# controllerBackup.net
KiCad netlist of a schematic drawn in EAGLE
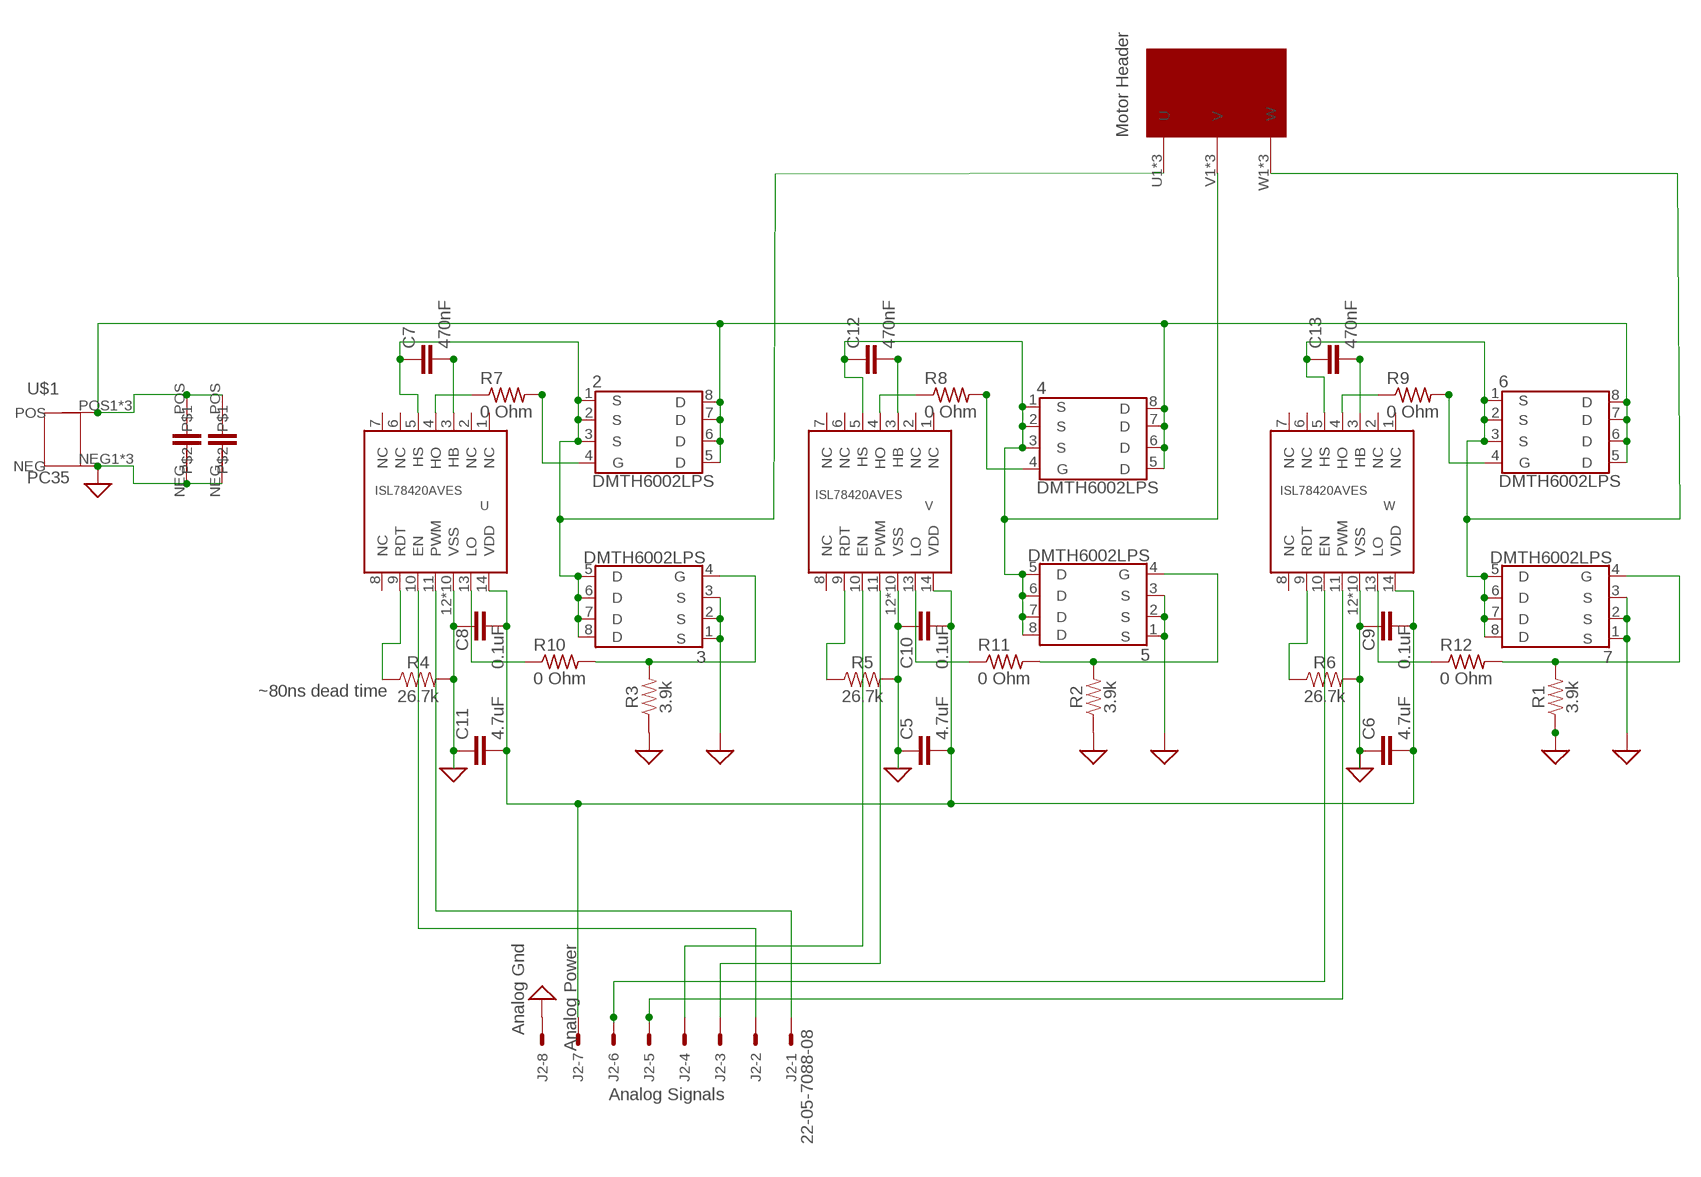
[diagram p0: schematic, sheet 1]

(export (version "E")
  (design (tool "Eeschema 10.0.6"))
  (components
    (comp (ref "2")
      (value "DMTH6002LPS")
      (footprint "eagle-import:POWERDI5060")
      (libsource (lib "eagle-import") (part "DMTH6002LPS"))
    )
    (comp (ref "3")
      (value "DMTH6002LPS")
      (footprint "eagle-import:POWERDI5060")
      (libsource (lib "eagle-import") (part "DMTH6002LPS"))
    )
    (comp (ref "4")
      (value "DMTH6002LPS")
      (footprint "eagle-import:POWERDI5060")
      (libsource (lib "eagle-import") (part "DMTH6002LPS"))
    )
    (comp (ref "5")
      (value "DMTH6002LPS")
      (footprint "eagle-import:POWERDI5060")
      (libsource (lib "eagle-import") (part "DMTH6002LPS"))
    )
    (comp (ref "6")
      (value "DMTH6002LPS")
      (footprint "eagle-import:POWERDI5060")
      (libsource (lib "eagle-import") (part "DMTH6002LPS"))
    )
    (comp (ref "7")
      (value "DMTH6002LPS")
      (footprint "eagle-import:POWERDI5060")
      (libsource (lib "eagle-import") (part "DMTH6002LPS"))
    )
    (comp (ref "C5")
      (value "4.7uF")
      (footprint "eagle-import:0603")
      (libsource (lib "eagle-import") (part "4.7UF0603"))
    )
    (comp (ref "C6")
      (value "4.7uF")
      (footprint "eagle-import:0603")
      (libsource (lib "eagle-import") (part "4.7UF0603"))
    )
    (comp (ref "C7")
      (value "470nF")
      (footprint "eagle-import:0402")
      (libsource (lib "eagle-import") (part "470NF-0402-16V-10%"))
    )
    (comp (ref "C8")
      (value "0.1uF")
      (footprint "eagle-import:0603")
      (libsource (lib "eagle-import") (part "0.1UF-0603-25V-(+80/-20%)"))
    )
    (comp (ref "C9")
      (value "0.1uF")
      (footprint "eagle-import:0603")
      (libsource (lib "eagle-import") (part "0.1UF-0603-25V-(+80/-20%)"))
    )
    (comp (ref "C10")
      (value "0.1uF")
      (footprint "eagle-import:0603")
      (libsource (lib "eagle-import") (part "0.1UF-0603-25V-(+80/-20%)"))
    )
    (comp (ref "C11")
      (value "4.7uF")
      (footprint "eagle-import:0603")
      (libsource (lib "eagle-import") (part "4.7UF0603"))
    )
    (comp (ref "C12")
      (value "470nF")
      (footprint "eagle-import:0402")
      (libsource (lib "eagle-import") (part "470NF-0402-16V-10%"))
    )
    (comp (ref "C13")
      (value "470nF")
      (footprint "eagle-import:0402")
      (libsource (lib "eagle-import") (part "470NF-0402-16V-10%"))
    )
    (comp (ref "J2")
      (value "22-05-7088-08")
      (footprint "eagle-import:7395-08")
      (fields (field (name "MF") "MOLEX"))
      (libsource (lib "eagle-import") (part "22-?-0805-7088"))
    )
    (comp (ref "R1")
      (value "3.9k")
      (footprint "eagle-import:0603")
      (libsource (lib "eagle-import") (part "3.9KOHM-0603-1/10W-1%"))
    )
    (comp (ref "R2")
      (value "3.9k")
      (footprint "eagle-import:0603")
      (libsource (lib "eagle-import") (part "3.9KOHM-0603-1/10W-1%"))
    )
    (comp (ref "R3")
      (value "3.9k")
      (footprint "eagle-import:0603")
      (libsource (lib "eagle-import") (part "3.9KOHM-0603-1/10W-1%"))
    )
    (comp (ref "R4")
      (value "26.7k")
      (footprint "eagle-import:0603")
      (libsource (lib "eagle-import") (part "26.7KOHM0603-1/10W-1%"))
    )
    (comp (ref "R5")
      (value "26.7k")
      (footprint "eagle-import:0603")
      (libsource (lib "eagle-import") (part "26.7KOHM0603-1/10W-1%"))
    )
    (comp (ref "R6")
      (value "26.7k")
      (footprint "eagle-import:0603")
      (libsource (lib "eagle-import") (part "26.7KOHM0603-1/10W-1%"))
    )
    (comp (ref "R7")
      (value "0 Ohm")
      (footprint "eagle-import:R0603")
      (libsource (lib "eagle-import") (part "R-US_R0603"))
    )
    (comp (ref "R8")
      (value "0 Ohm")
      (footprint "eagle-import:R0603")
      (libsource (lib "eagle-import") (part "R-US_R0603"))
    )
    (comp (ref "R9")
      (value "0 Ohm")
      (footprint "eagle-import:R0603")
      (libsource (lib "eagle-import") (part "R-US_R0603"))
    )
    (comp (ref "R10")
      (value "0 Ohm")
      (footprint "eagle-import:R0603")
      (libsource (lib "eagle-import") (part "R-US_R0603"))
    )
    (comp (ref "R11")
      (value "0 Ohm")
      (footprint "eagle-import:R0603")
      (libsource (lib "eagle-import") (part "R-US_R0603"))
    )
    (comp (ref "R12")
      (value "0 Ohm")
      (footprint "eagle-import:R0603")
      (libsource (lib "eagle-import") (part "R-US_R0603"))
    )
    (comp (ref "U")
      (value "ISL78420AVES")
      (footprint "eagle-import:14LDHTSSOP")
      (libsource (lib "eagle-import") (part "ISL78420AVES"))
    )
    (comp (ref "U$1")
      (value "PC35")
      (footprint "eagle-import:PC35.1762741")
      (libsource (lib "eagle-import") (part "PC35"))
    )
    (comp (ref "U$2")
      (value "PC35_3")
      (footprint "eagle-import:PC35.1762754")
      (libsource (lib "eagle-import") (part "PC35_3"))
    )
    (comp (ref "U$3")
      (value "1mF 63V")
      (footprint "eagle-import:MAL2146998")
      (libsource (lib "eagle-import") (part "VISHAYCAP"))
    )
    (comp (ref "U$4")
      (value "1mF 63V")
      (footprint "eagle-import:MAL2146998")
      (libsource (lib "eagle-import") (part "VISHAYCAP"))
    )
    (comp (ref "V")
      (value "ISL78420AVES")
      (footprint "eagle-import:14LDHTSSOP")
      (libsource (lib "eagle-import") (part "ISL78420AVES"))
    )
    (comp (ref "W")
      (value "ISL78420AVES")
      (footprint "eagle-import:14LDHTSSOP")
      (libsource (lib "eagle-import") (part "ISL78420AVES"))
    )
  )
  (nets
    (net (code "1") (name "Net-(2-G)") (class "Default")
      (node (ref "2") (pin "4") (pinfunction "G_4") (pintype "bidirectional"))
      (node (ref "R7") (pin "2") (pinfunction "2_2") (pintype "passive"))
    )
    (net (code "2") (name "Net-(3-G)") (class "Default")
      (node (ref "3") (pin "4") (pinfunction "G_4") (pintype "bidirectional"))
      (node (ref "R10") (pin "2") (pinfunction "2_2") (pintype "passive"))
      (node (ref "R3") (pin "2") (pinfunction "2_2") (pintype "passive"))
    )
    (net (code "3") (name "Net-(4-G)") (class "Default")
      (node (ref "4") (pin "4") (pinfunction "G_4") (pintype "bidirectional"))
      (node (ref "R8") (pin "2") (pinfunction "2_2") (pintype "passive"))
    )
    (net (code "4") (name "Net-(5-G)") (class "Default")
      (node (ref "5") (pin "4") (pinfunction "G_4") (pintype "bidirectional"))
      (node (ref "R11") (pin "2") (pinfunction "2_2") (pintype "passive"))
      (node (ref "R2") (pin "2") (pinfunction "2_2") (pintype "passive"))
    )
    (net (code "5") (name "Net-(6-G)") (class "Default")
      (node (ref "6") (pin "4") (pinfunction "G_4") (pintype "bidirectional"))
      (node (ref "R9") (pin "2") (pinfunction "2_2") (pintype "passive"))
    )
    (net (code "6") (name "Net-(7-G)") (class "Default")
      (node (ref "7") (pin "4") (pinfunction "G_4") (pintype "bidirectional"))
      (node (ref "R1") (pin "2") (pinfunction "2_2") (pintype "passive"))
      (node (ref "R12") (pin "2") (pinfunction "2_2") (pintype "passive"))
    )
    (net (code "7") (name "Net-(J2A-S)") (class "Default")
      (node (ref "J2") (pin "1") (pinfunction "S_1") (pintype "passive"))
      (node (ref "U") (pin "11") (pinfunction "PWM_11") (pintype "bidirectional"))
    )
    (net (code "8") (name "Net-(J2B-S)") (class "Default")
      (node (ref "J2") (pin "2") (pinfunction "S_2") (pintype "passive"))
      (node (ref "U") (pin "10") (pinfunction "EN_10") (pintype "bidirectional"))
    )
    (net (code "9") (name "Net-(J2C-S)") (class "Default")
      (node (ref "J2") (pin "3") (pinfunction "S_3") (pintype "passive"))
      (node (ref "V") (pin "11") (pinfunction "PWM_11") (pintype "bidirectional"))
    )
    (net (code "10") (name "Net-(J2D-S)") (class "Default")
      (node (ref "J2") (pin "4") (pinfunction "S_4") (pintype "passive"))
      (node (ref "V") (pin "10") (pinfunction "EN_10") (pintype "bidirectional"))
    )
    (net (code "11") (name "Net-(J2E-S)") (class "Default")
      (node (ref "J2") (pin "5") (pinfunction "S_5") (pintype "passive"))
      (node (ref "W") (pin "11") (pinfunction "PWM_11") (pintype "bidirectional"))
    )
    (net (code "12") (name "Net-(J2F-S)") (class "Default")
      (node (ref "J2") (pin "6") (pinfunction "S_6") (pintype "passive"))
      (node (ref "W") (pin "10") (pinfunction "EN_10") (pintype "bidirectional"))
    )
    (net (code "13") (name "Net-(J2G-S)") (class "Default")
      (node (ref "C10") (pin "2") (pinfunction "2_2") (pintype "passive"))
      (node (ref "C11") (pin "2") (pinfunction "2_2") (pintype "passive"))
      (node (ref "C5") (pin "2") (pinfunction "2_2") (pintype "passive"))
      (node (ref "C6") (pin "2") (pinfunction "2_2") (pintype "passive"))
      (node (ref "C8") (pin "2") (pinfunction "2_2") (pintype "passive"))
      (node (ref "C9") (pin "2") (pinfunction "2_2") (pintype "passive"))
      (node (ref "J2") (pin "7") (pinfunction "S_7") (pintype "passive"))
      (node (ref "U") (pin "14") (pinfunction "VDD_14") (pintype "bidirectional"))
      (node (ref "V") (pin "14") (pinfunction "VDD_14") (pintype "bidirectional"))
      (node (ref "W") (pin "14") (pinfunction "VDD_14") (pintype "bidirectional"))
    )
    (net (code "14") (name "Net-(U$3-P$2)") (class "Default")
      (node (ref "2") (pin "5") (pinfunction "D_5") (pintype "bidirectional"))
      (node (ref "2") (pin "6") (pinfunction "D_6") (pintype "bidirectional"))
      (node (ref "2") (pin "7") (pinfunction "D_7") (pintype "bidirectional"))
      (node (ref "2") (pin "8") (pinfunction "D_8") (pintype "bidirectional"))
      (node (ref "4") (pin "5") (pinfunction "D_5") (pintype "bidirectional"))
      (node (ref "4") (pin "6") (pinfunction "D_6") (pintype "bidirectional"))
      (node (ref "4") (pin "7") (pinfunction "D_7") (pintype "bidirectional"))
      (node (ref "4") (pin "8") (pinfunction "D_8") (pintype "bidirectional"))
      (node (ref "6") (pin "5") (pinfunction "D_5") (pintype "bidirectional"))
      (node (ref "6") (pin "6") (pinfunction "D_6") (pintype "bidirectional"))
      (node (ref "6") (pin "7") (pinfunction "D_7") (pintype "bidirectional"))
      (node (ref "6") (pin "8") (pinfunction "D_8") (pintype "bidirectional"))
      (node (ref "U$1") (pin "POS1") (pinfunction "POS_POS1") (pintype "bidirectional"))
      (node (ref "U$1") (pin "POS2") (pinfunction "POS_POS2") (pintype "bidirectional"))
      (node (ref "U$1") (pin "POS3") (pinfunction "POS_POS3") (pintype "bidirectional"))
      (node (ref "U$3") (pin "POS") (pinfunction "P$2_POS") (pintype "bidirectional"))
      (node (ref "U$4") (pin "POS") (pinfunction "P$2_POS") (pintype "bidirectional"))
    )
    (net (code "15") (name "Net-(U-HB)") (class "Default")
      (node (ref "C7") (pin "2") (pinfunction "2_2") (pintype "passive"))
      (node (ref "U") (pin "3") (pinfunction "HB_3") (pintype "bidirectional"))
    )
    (net (code "16") (name "Net-(U-HO)") (class "Default")
      (node (ref "R7") (pin "1") (pinfunction "1_1") (pintype "passive"))
      (node (ref "U") (pin "4") (pinfunction "HO_4") (pintype "bidirectional"))
    )
    (net (code "17") (name "Net-(U-HS)") (class "Default")
      (node (ref "2") (pin "1") (pinfunction "S_1") (pintype "bidirectional"))
      (node (ref "2") (pin "2") (pinfunction "S_2") (pintype "bidirectional"))
      (node (ref "2") (pin "3") (pinfunction "S_3") (pintype "bidirectional"))
      (node (ref "3") (pin "5") (pinfunction "D_5") (pintype "bidirectional"))
      (node (ref "3") (pin "6") (pinfunction "D_6") (pintype "bidirectional"))
      (node (ref "3") (pin "7") (pinfunction "D_7") (pintype "bidirectional"))
      (node (ref "3") (pin "8") (pinfunction "D_8") (pintype "bidirectional"))
      (node (ref "C7") (pin "1") (pinfunction "1_1") (pintype "passive"))
      (node (ref "U") (pin "5") (pinfunction "HS_5") (pintype "bidirectional"))
      (node (ref "U$2") (pin "U1") (pinfunction "U_U1") (pintype "bidirectional"))
      (node (ref "U$2") (pin "U2") (pinfunction "U_U2") (pintype "bidirectional"))
      (node (ref "U$2") (pin "U3") (pinfunction "U_U3") (pintype "bidirectional"))
    )
    (net (code "18") (name "Net-(U-LO)") (class "Default")
      (node (ref "R10") (pin "1") (pinfunction "1_1") (pintype "passive"))
      (node (ref "U") (pin "13") (pinfunction "LO_13") (pintype "bidirectional"))
    )
    (net (code "19") (name "Net-(U-RDT)") (class "Default")
      (node (ref "R4") (pin "1") (pinfunction "1_1") (pintype "passive"))
      (node (ref "U") (pin "9") (pinfunction "RDT_9") (pintype "bidirectional"))
    )
    (net (code "20") (name "Net-(V-HB)") (class "Default")
      (node (ref "C12") (pin "2") (pinfunction "2_2") (pintype "passive"))
      (node (ref "V") (pin "3") (pinfunction "HB_3") (pintype "bidirectional"))
    )
    (net (code "21") (name "Net-(V-HO)") (class "Default")
      (node (ref "R8") (pin "1") (pinfunction "1_1") (pintype "passive"))
      (node (ref "V") (pin "4") (pinfunction "HO_4") (pintype "bidirectional"))
    )
    (net (code "22") (name "Net-(V-HS)") (class "Default")
      (node (ref "4") (pin "1") (pinfunction "S_1") (pintype "bidirectional"))
      (node (ref "4") (pin "2") (pinfunction "S_2") (pintype "bidirectional"))
      (node (ref "4") (pin "3") (pinfunction "S_3") (pintype "bidirectional"))
      (node (ref "5") (pin "5") (pinfunction "D_5") (pintype "bidirectional"))
      (node (ref "5") (pin "6") (pinfunction "D_6") (pintype "bidirectional"))
      (node (ref "5") (pin "7") (pinfunction "D_7") (pintype "bidirectional"))
      (node (ref "5") (pin "8") (pinfunction "D_8") (pintype "bidirectional"))
      (node (ref "C12") (pin "1") (pinfunction "1_1") (pintype "passive"))
      (node (ref "U$2") (pin "V1") (pinfunction "V_V1") (pintype "bidirectional"))
      (node (ref "U$2") (pin "V2") (pinfunction "V_V2") (pintype "bidirectional"))
      (node (ref "U$2") (pin "V3") (pinfunction "V_V3") (pintype "bidirectional"))
      (node (ref "V") (pin "5") (pinfunction "HS_5") (pintype "bidirectional"))
    )
    (net (code "23") (name "Net-(V-LO)") (class "Default")
      (node (ref "R11") (pin "1") (pinfunction "1_1") (pintype "passive"))
      (node (ref "V") (pin "13") (pinfunction "LO_13") (pintype "bidirectional"))
    )
    (net (code "24") (name "Net-(V-RDT)") (class "Default")
      (node (ref "R5") (pin "1") (pinfunction "1_1") (pintype "passive"))
      (node (ref "V") (pin "9") (pinfunction "RDT_9") (pintype "bidirectional"))
    )
    (net (code "25") (name "Net-(W-HB)") (class "Default")
      (node (ref "C13") (pin "2") (pinfunction "2_2") (pintype "passive"))
      (node (ref "W") (pin "3") (pinfunction "HB_3") (pintype "bidirectional"))
    )
    (net (code "26") (name "Net-(W-HO)") (class "Default")
      (node (ref "R9") (pin "1") (pinfunction "1_1") (pintype "passive"))
      (node (ref "W") (pin "4") (pinfunction "HO_4") (pintype "bidirectional"))
    )
    (net (code "27") (name "Net-(W-HS)") (class "Default")
      (node (ref "6") (pin "1") (pinfunction "S_1") (pintype "bidirectional"))
      (node (ref "6") (pin "2") (pinfunction "S_2") (pintype "bidirectional"))
      (node (ref "6") (pin "3") (pinfunction "S_3") (pintype "bidirectional"))
      (node (ref "7") (pin "5") (pinfunction "D_5") (pintype "bidirectional"))
      (node (ref "7") (pin "6") (pinfunction "D_6") (pintype "bidirectional"))
      (node (ref "7") (pin "7") (pinfunction "D_7") (pintype "bidirectional"))
      (node (ref "7") (pin "8") (pinfunction "D_8") (pintype "bidirectional"))
      (node (ref "C13") (pin "1") (pinfunction "1_1") (pintype "passive"))
      (node (ref "U$2") (pin "W1") (pinfunction "W_W1") (pintype "bidirectional"))
      (node (ref "U$2") (pin "W2") (pinfunction "W_W2") (pintype "bidirectional"))
      (node (ref "U$2") (pin "W3") (pinfunction "W_W3") (pintype "bidirectional"))
      (node (ref "W") (pin "5") (pinfunction "HS_5") (pintype "bidirectional"))
    )
    (net (code "28") (name "Net-(W-LO)") (class "Default")
      (node (ref "R12") (pin "1") (pinfunction "1_1") (pintype "passive"))
      (node (ref "W") (pin "13") (pinfunction "LO_13") (pintype "bidirectional"))
    )
    (net (code "29") (name "Net-(W-RDT)") (class "Default")
      (node (ref "R6") (pin "1") (pinfunction "1_1") (pintype "passive"))
      (node (ref "W") (pin "9") (pinfunction "RDT_9") (pintype "bidirectional"))
    )
    (net (code "30") (name "SUP") (class "Default")
      (node (ref "3") (pin "1") (pinfunction "S_1") (pintype "bidirectional"))
      (node (ref "3") (pin "2") (pinfunction "S_2") (pintype "bidirectional"))
      (node (ref "3") (pin "3") (pinfunction "S_3") (pintype "bidirectional"))
      (node (ref "5") (pin "1") (pinfunction "S_1") (pintype "bidirectional"))
      (node (ref "5") (pin "2") (pinfunction "S_2") (pintype "bidirectional"))
      (node (ref "5") (pin "3") (pinfunction "S_3") (pintype "bidirectional"))
      (node (ref "7") (pin "1") (pinfunction "S_1") (pintype "bidirectional"))
      (node (ref "7") (pin "2") (pinfunction "S_2") (pintype "bidirectional"))
      (node (ref "7") (pin "3") (pinfunction "S_3") (pintype "bidirectional"))
      (node (ref "C10") (pin "1") (pinfunction "1_1") (pintype "passive"))
      (node (ref "C11") (pin "1") (pinfunction "1_1") (pintype "passive"))
      (node (ref "C5") (pin "1") (pinfunction "1_1") (pintype "passive"))
      (node (ref "C6") (pin "1") (pinfunction "1_1") (pintype "passive"))
      (node (ref "C8") (pin "1") (pinfunction "1_1") (pintype "passive"))
      (node (ref "C9") (pin "1") (pinfunction "1_1") (pintype "passive"))
      (node (ref "J2") (pin "8") (pinfunction "S_8") (pintype "passive"))
      (node (ref "R1") (pin "1") (pinfunction "1_1") (pintype "passive"))
      (node (ref "R2") (pin "1") (pinfunction "1_1") (pintype "passive"))
      (node (ref "R3") (pin "1") (pinfunction "1_1") (pintype "passive"))
      (node (ref "R4") (pin "2") (pinfunction "2_2") (pintype "passive"))
      (node (ref "R5") (pin "2") (pinfunction "2_2") (pintype "passive"))
      (node (ref "R6") (pin "2") (pinfunction "2_2") (pintype "passive"))
      (node (ref "U") (pin "12") (pinfunction "VSS_12") (pintype "bidirectional"))
      (node (ref "U") (pin "EPAD") (pinfunction "VSS_EPAD") (pintype "bidirectional"))
      (node (ref "U") (pin "P$1") (pinfunction "VSS_P$1") (pintype "bidirectional"))
      (node (ref "U") (pin "P$2") (pinfunction "VSS_P$2") (pintype "bidirectional"))
      (node (ref "U") (pin "P$3") (pinfunction "VSS_P$3") (pintype "bidirectional"))
      (node (ref "U") (pin "P$4") (pinfunction "VSS_P$4") (pintype "bidirectional"))
      (node (ref "U") (pin "P$5") (pinfunction "VSS_P$5") (pintype "bidirectional"))
      (node (ref "U") (pin "P$6") (pinfunction "VSS_P$6") (pintype "bidirectional"))
      (node (ref "U") (pin "P$7") (pinfunction "VSS_P$7") (pintype "bidirectional"))
      (node (ref "U") (pin "P$8") (pinfunction "VSS_P$8") (pintype "bidirectional"))
      (node (ref "U$1") (pin "NEG1") (pinfunction "NEG_NEG1") (pintype "bidirectional"))
      (node (ref "U$1") (pin "NEG2") (pinfunction "NEG_NEG2") (pintype "bidirectional"))
      (node (ref "U$1") (pin "NEG3") (pinfunction "NEG_NEG3") (pintype "bidirectional"))
      (node (ref "U$3") (pin "NEG") (pinfunction "P$1_NEG") (pintype "bidirectional"))
      (node (ref "U$4") (pin "NEG") (pinfunction "P$1_NEG") (pintype "bidirectional"))
      (node (ref "V") (pin "12") (pinfunction "VSS_12") (pintype "bidirectional"))
      (node (ref "V") (pin "EPAD") (pinfunction "VSS_EPAD") (pintype "bidirectional"))
      (node (ref "V") (pin "P$1") (pinfunction "VSS_P$1") (pintype "bidirectional"))
      (node (ref "V") (pin "P$2") (pinfunction "VSS_P$2") (pintype "bidirectional"))
      (node (ref "V") (pin "P$3") (pinfunction "VSS_P$3") (pintype "bidirectional"))
      (node (ref "V") (pin "P$4") (pinfunction "VSS_P$4") (pintype "bidirectional"))
      (node (ref "V") (pin "P$5") (pinfunction "VSS_P$5") (pintype "bidirectional"))
      (node (ref "V") (pin "P$6") (pinfunction "VSS_P$6") (pintype "bidirectional"))
      (node (ref "V") (pin "P$7") (pinfunction "VSS_P$7") (pintype "bidirectional"))
      (node (ref "V") (pin "P$8") (pinfunction "VSS_P$8") (pintype "bidirectional"))
      (node (ref "W") (pin "12") (pinfunction "VSS_12") (pintype "bidirectional"))
      (node (ref "W") (pin "EPAD") (pinfunction "VSS_EPAD") (pintype "bidirectional"))
      (node (ref "W") (pin "P$1") (pinfunction "VSS_P$1") (pintype "bidirectional"))
      (node (ref "W") (pin "P$2") (pinfunction "VSS_P$2") (pintype "bidirectional"))
      (node (ref "W") (pin "P$3") (pinfunction "VSS_P$3") (pintype "bidirectional"))
      (node (ref "W") (pin "P$4") (pinfunction "VSS_P$4") (pintype "bidirectional"))
      (node (ref "W") (pin "P$5") (pinfunction "VSS_P$5") (pintype "bidirectional"))
      (node (ref "W") (pin "P$6") (pinfunction "VSS_P$6") (pintype "bidirectional"))
      (node (ref "W") (pin "P$7") (pinfunction "VSS_P$7") (pintype "bidirectional"))
      (node (ref "W") (pin "P$8") (pinfunction "VSS_P$8") (pintype "bidirectional"))
    )
    (net (code "31") (name "unconnected-(U-NC-Pad1)") (class "Default")
      (node (ref "U") (pin "1") (pinfunction "NC_1") (pintype "bidirectional"))
    )
    (net (code "32") (name "unconnected-(U-NC-Pad2)") (class "Default")
      (node (ref "U") (pin "2") (pinfunction "NC_2") (pintype "bidirectional"))
    )
    (net (code "33") (name "unconnected-(U-NC-Pad6)") (class "Default")
      (node (ref "U") (pin "6") (pinfunction "NC_6") (pintype "bidirectional"))
    )
    (net (code "34") (name "unconnected-(U-NC-Pad7)") (class "Default")
      (node (ref "U") (pin "7") (pinfunction "NC_7") (pintype "bidirectional"))
    )
    (net (code "35") (name "unconnected-(U-NC-Pad8)") (class "Default")
      (node (ref "U") (pin "8") (pinfunction "NC_8") (pintype "bidirectional"))
    )
    (net (code "36") (name "unconnected-(V-NC-Pad1)") (class "Default")
      (node (ref "V") (pin "1") (pinfunction "NC_1") (pintype "bidirectional"))
    )
    (net (code "37") (name "unconnected-(V-NC-Pad2)") (class "Default")
      (node (ref "V") (pin "2") (pinfunction "NC_2") (pintype "bidirectional"))
    )
    (net (code "38") (name "unconnected-(V-NC-Pad6)") (class "Default")
      (node (ref "V") (pin "6") (pinfunction "NC_6") (pintype "bidirectional"))
    )
    (net (code "39") (name "unconnected-(V-NC-Pad7)") (class "Default")
      (node (ref "V") (pin "7") (pinfunction "NC_7") (pintype "bidirectional"))
    )
    (net (code "40") (name "unconnected-(V-NC-Pad8)") (class "Default")
      (node (ref "V") (pin "8") (pinfunction "NC_8") (pintype "bidirectional"))
    )
    (net (code "41") (name "unconnected-(W-NC-Pad1)") (class "Default")
      (node (ref "W") (pin "1") (pinfunction "NC_1") (pintype "bidirectional"))
    )
    (net (code "42") (name "unconnected-(W-NC-Pad2)") (class "Default")
      (node (ref "W") (pin "2") (pinfunction "NC_2") (pintype "bidirectional"))
    )
    (net (code "43") (name "unconnected-(W-NC-Pad6)") (class "Default")
      (node (ref "W") (pin "6") (pinfunction "NC_6") (pintype "bidirectional"))
    )
    (net (code "44") (name "unconnected-(W-NC-Pad7)") (class "Default")
      (node (ref "W") (pin "7") (pinfunction "NC_7") (pintype "bidirectional"))
    )
    (net (code "45") (name "unconnected-(W-NC-Pad8)") (class "Default")
      (node (ref "W") (pin "8") (pinfunction "NC_8") (pintype "bidirectional"))
    )
  )
)
